# LM2587.net
KiCad netlist of a schematic drawn in Altium Designer
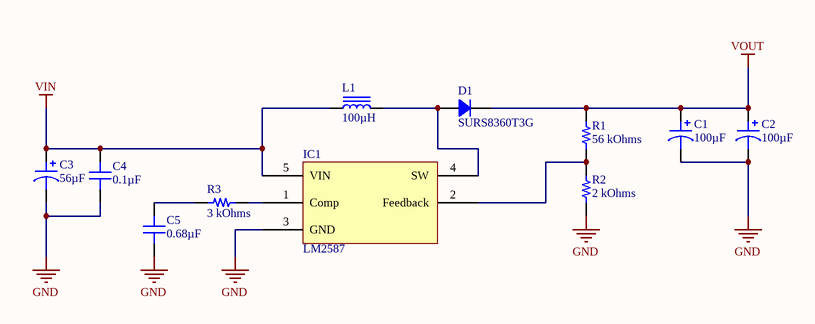
[diagram p0: LM2587.SchDoc]

(export (version "E")
  (design (tool "Eeschema 10.0.6"))
  (components
    (comp (ref "C1")
      (value "100µF")
      (footprint "CAP ALSMD 8.3MM H10.5MM")
      (description "CAP ALUM 100UF 20% 50V SMD")
      (fields
        (field (name "PART NUMBER") "EEE-FK1H101P")
        (field (name "MANUFACTURER") "Panasonic Electronic Components")
      )
      (libsource (lib "Celestial Altium Library - altium_library") (part "Polarised Capacitor"))
    )
    (comp (ref "C2")
      (value "100µF")
      (footprint "CAP ALSMD 8.3MM H10.5MM")
      (description "CAP ALUM 100UF 20% 50V SMD")
      (fields
        (field (name "PART NUMBER") "EEE-FK1H101P")
        (field (name "MANUFACTURER") "Panasonic Electronic Components")
      )
      (libsource (lib "Celestial Altium Library - altium_library") (part "Polarised Capacitor"))
    )
    (comp (ref "C3")
      (value "56µF")
      (footprint "CAP ALSMD 6.6MM H7.7MM")
      (description "CAP ALUM 56UF 20% 35V SMD")
      (fields (field (name "PART NUMBER") "UWD1V560MCL1GS") (field (name "MANUFACTURER") "Nichicon"))
      (libsource (lib "Celestial Altium Library - altium_library") (part "Polarised Capacitor"))
    )
    (comp (ref "C4")
      (value "0.1µF")
      (footprint "CAP 0805_2012")
      (description "CAP CER 0.1UF 50V X7R 0805")
      (fields (field (name "PART NUMBER") "CC0805JRX7R9BB104") (field (name "MANUFACTURER") "Yageo"))
      (libsource (lib "Celestial Altium Library - altium_library") (part "Capacitor"))
    )
    (comp (ref "C5")
      (value "0.68µF")
      (footprint "CAP 0805_2012")
      (description "CAP CER 0.68UF 50V X7R 0805")
      (fields (field (name "PART NUMBER") "C0805C684K5RACTU") (field (name "MANUFACTURER") "KEMET"))
      (libsource (lib "Celestial Altium Library - altium_library") (part "Capacitor"))
    )
    (comp (ref "D1")
      (value "SURS8360T3G")
      (footprint "DO214AB SMC")
      (description "DIODE GEN PURP 600V 3A SMC")
      (fields (field (name "MANUFACTURER") "ON Semiconductor"))
      (libsource (lib "Celestial Altium Library - altium_library") (part "Diode"))
    )
    (comp (ref "IC1")
      (value "LM2587")
      (footprint "AltiumLive:D2PAK")
      (description "Boost Converter")
      (libsource (lib "AltiumLive") (part "LM2587"))
    )
    (comp (ref "L1")
      (value "100µH")
      (footprint "AltiumLive:7447070")
      (description "FIXED IND 100UH 2.1A 150MOHM SMD")
      (fields (field (name "PART NUMBER") "SRR1280-101M") (field (name "MANUFACTURER") "Bourns Inc."))
      (libsource (lib "Celestial Altium Library - altium_library") (part "Inductor"))
    )
    (comp (ref "R1")
      (value "56 kOhms")
      (footprint "RES 0805_2012")
      (description "RES 56K OHM 1% 1/8W 0805")
      (fields
        (field (name "PART NUMBER") "RMCF0805FT56K0")
        (field (name "MANUFACTURER") "Stackpole Electronics Inc")
      )
      (libsource (lib "Celestial Altium Library - altium_library") (part "Resistor"))
    )
    (comp (ref "R2")
      (value "2 kOhms")
      (footprint "RES 0805_2012")
      (description "RES SMD 2K OHM 1% 1/8W 0805")
      (fields (field (name "PART NUMBER") "AC0805FR-072KL") (field (name "MANUFACTURER") "Yageo"))
      (libsource (lib "Celestial Altium Library - altium_library") (part "Resistor"))
    )
    (comp (ref "R3")
      (value "3 kOhms")
      (footprint "RES 0805_2012")
      (description "RES SMD 3K OHM 1% 1/8W 0805")
      (fields
        (field (name "PART NUMBER") "ERJ-6ENF3001V")
        (field (name "MANUFACTURER") "Panasonic Electronic Components")
      )
      (libsource (lib "Celestial Altium Library - altium_library") (part "Resistor"))
    )
  )
  (nets
    (net (code "1") (name "GND") (class "Default")
      (node (ref "C1") (pin "2") (pinfunction "2_2") (pintype "passive"))
      (node (ref "C2") (pin "2") (pinfunction "2_2") (pintype "passive"))
      (node (ref "C3") (pin "2") (pinfunction "2_2") (pintype "passive"))
      (node (ref "C4") (pin "1") (pinfunction "1_1") (pintype "passive"))
      (node (ref "C5") (pin "1") (pinfunction "1_1") (pintype "passive"))
      (node (ref "IC1") (pin "3") (pinfunction "GND_3") (pintype "passive"))
      (node (ref "R2") (pin "1") (pinfunction "1_1") (pintype "passive"))
    )
    (net (code "2") (name "Net-(C5-Pad2)") (class "Default")
      (node (ref "C5") (pin "2") (pinfunction "2_2") (pintype "passive"))
      (node (ref "R3") (pin "2") (pinfunction "2_2") (pintype "passive"))
    )
    (net (code "3") (name "Net-(IC1-Comp)") (class "Default")
      (node (ref "IC1") (pin "1") (pinfunction "Comp_1") (pintype "passive"))
      (node (ref "R3") (pin "1") (pinfunction "1_1") (pintype "passive"))
    )
    (net (code "4") (name "Net-(IC1-Feedback)") (class "Default")
      (node (ref "IC1") (pin "2") (pinfunction "Feedback_2") (pintype "passive"))
      (node (ref "R1") (pin "1") (pinfunction "1_1") (pintype "passive"))
      (node (ref "R2") (pin "2") (pinfunction "2_2") (pintype "passive"))
    )
    (net (code "5") (name "Net-(IC1-SW)") (class "Default")
      (node (ref "D1") (pin "1") (pinfunction "1_1") (pintype "passive"))
      (node (ref "IC1") (pin "4") (pinfunction "SW_4") (pintype "passive"))
      (node (ref "L1") (pin "2") (pinfunction "2_2") (pintype "passive"))
    )
    (net (code "6") (name "VIN") (class "Default")
      (node (ref "C3") (pin "1") (pinfunction "1_1") (pintype "passive"))
      (node (ref "C4") (pin "2") (pinfunction "2_2") (pintype "passive"))
      (node (ref "IC1") (pin "5") (pinfunction "VIN_5") (pintype "passive"))
      (node (ref "L1") (pin "1") (pinfunction "1_1") (pintype "passive"))
    )
    (net (code "7") (name "VOUT") (class "Default")
      (node (ref "C1") (pin "1") (pinfunction "1_1") (pintype "passive"))
      (node (ref "C2") (pin "1") (pinfunction "1_1") (pintype "passive"))
      (node (ref "D1") (pin "2") (pinfunction "2_2") (pintype "passive"))
      (node (ref "R1") (pin "2") (pinfunction "2_2") (pintype "passive"))
    )
  )
)
